# Grove_LED.net
KiCad netlist of a schematic drawn in EAGLE
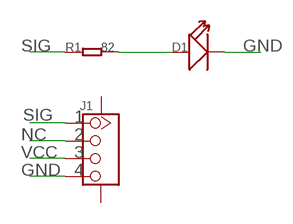
[diagram p0: schematic, sheet 1]

(export (version "E")
  (design (tool "Eeschema 10.0.6"))
  (components
    (comp (ref "D1")
      (value "LED-3MM")
      (footprint "eagle-import:LED-2P-2.54-3MM")
      (libsource (lib "eagle-import") (part "LED-3MM"))
    )
    (comp (ref "J1")
      (value "TWIG-4P-2.0-SMD-FEMALE-REINFORCE'90D'")
      (footprint "eagle-import:4P-SMD-2.0-90D")
      (libsource (lib "eagle-import") (part "TWIG-4P-2.0-SMD-FEMALE-REINFORCE'90D'"))
    )
    (comp (ref "R1")
      (value "82")
      (footprint "eagle-import:1206")
      (libsource (lib "eagle-import") (part "R-1206"))
    )
  )
  (nets
    (net (code "1") (name "/GND") (class "Default")
      (node (ref "D1") (pin "K") (pinfunction "-_K") (pintype "passive"))
      (node (ref "J1") (pin "4") (pinfunction "4_4") (pintype "bidirectional"))
    )
    (net (code "2") (name "/SIG") (class "Default")
      (node (ref "J1") (pin "1") (pinfunction "1_1") (pintype "bidirectional"))
      (node (ref "R1") (pin "1") (pinfunction "1_1") (pintype "passive"))
    )
    (net (code "3") (name "Net-(D1-+)") (class "Default")
      (node (ref "D1") (pin "A") (pinfunction "+_A") (pintype "passive"))
      (node (ref "R1") (pin "2") (pinfunction "2_2") (pintype "passive"))
    )
    (net (code "4") (name "unconnected-(J1-Pad2)") (class "Default")
      (node (ref "J1") (pin "2") (pinfunction "2_2") (pintype "bidirectional"))
    )
    (net (code "5") (name "unconnected-(J1-Pad3)") (class "Default")
      (node (ref "J1") (pin "3") (pinfunction "3_3") (pintype "bidirectional"))
    )
    (net (code "6") (name "unconnected-(J1-PadSS1)") (class "Default")
      (node (ref "J1") (pin "SS1") (pinfunction "SS1_SS1") (pintype "bidirectional"))
    )
    (net (code "7") (name "unconnected-(J1-PadSS2)") (class "Default")
      (node (ref "J1") (pin "SS2") (pinfunction "SS2_SS2") (pintype "bidirectional"))
    )
  )
)
